# 02_Top_Level.net
KiCad netlist of a schematic drawn in Altium Designer
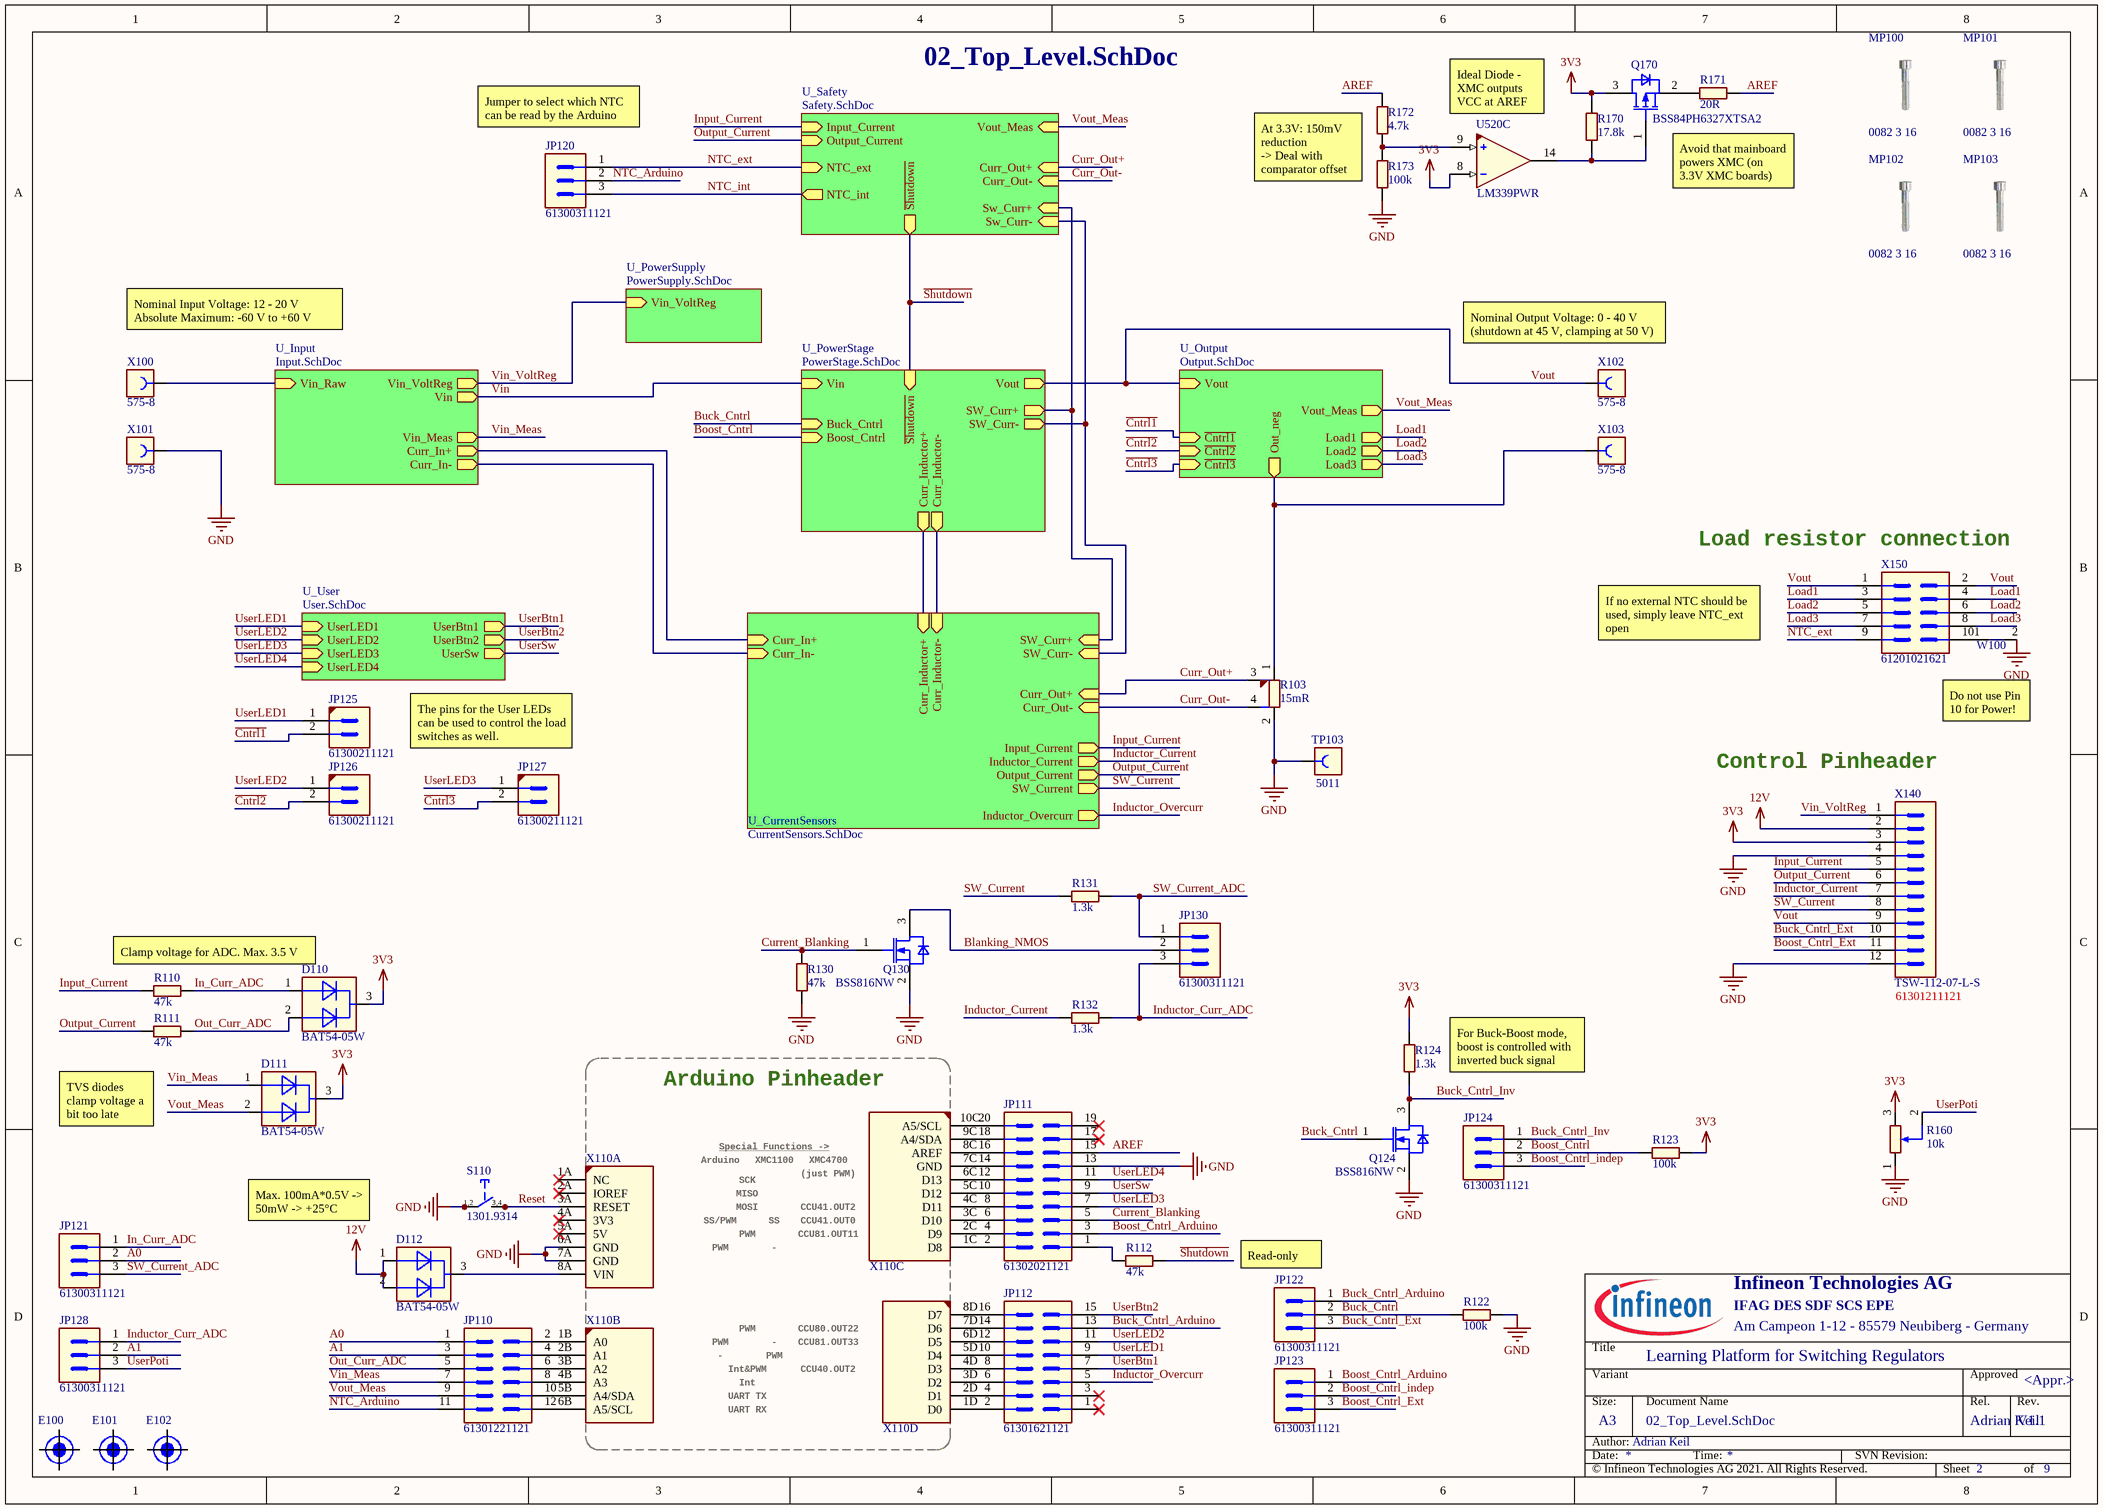
[diagram p0: 02_Top_Level.SchDoc]

(export (version "E")
  (design (tool "Eeschema 10.0.6"))
  (components
    (comp (ref "D110")
      (value "BAT54-05W")
      (footprint "SOT65P210X100-3N-1-V")
      (description "Silicon Schottky Diode, VR 30V")
      (fields (field (name "MANUFACTURER") "Infineon Technologies"))
      (libsource (lib "PCBLibraryData") (part "d_dual_a1a2c3_3p"))
    )
    (comp (ref "D111")
      (value "BAT54-05W")
      (footprint "SOT65P210X100-3N-1-V")
      (description "Silicon Schottky Diode, VR 30V")
      (fields (field (name "MANUFACTURER") "Infineon Technologies"))
      (libsource (lib "PCBLibraryData") (part "d_dual_a1a2c3_3p"))
    )
    (comp (ref "D112")
      (value "BAT54-05W")
      (footprint "SOT65P210X100-3N-1-V")
      (description "Silicon Schottky Diode, VR 30V")
      (fields (field (name "MANUFACTURER") "Infineon Technologies"))
      (libsource (lib "PCBLibraryData") (part "d_dual_a1a2c3_3p"))
    )
    (comp (ref "E100")
      (value "~")
      (footprint "fiducial")
      (description "Fiducial Mark")
      (fields
        (field (name "LEGACY PARTNUMBER") "MEC10000008")
        (field (name "MANUFACTURER") "Infineon Technologies")
      )
      (libsource (lib "PCBLibraryData") (part "fiducial"))
    )
    (comp (ref "E101")
      (value "~")
      (footprint "fiducial")
      (description "Fiducial Mark")
      (fields
        (field (name "LEGACY PARTNUMBER") "MEC10000008")
        (field (name "MANUFACTURER") "Infineon Technologies")
      )
      (libsource (lib "PCBLibraryData") (part "fiducial"))
    )
    (comp (ref "E102")
      (value "~")
      (footprint "fiducial")
      (description "Fiducial Mark")
      (fields
        (field (name "LEGACY PARTNUMBER") "MEC10000008")
        (field (name "MANUFACTURER") "Infineon Technologies")
      )
      (libsource (lib "PCBLibraryData") (part "fiducial"))
    )
    (comp (ref "JP110")
      (value "61301221121")
      (footprint "CON-M-THT-61301221121")
      (description "WR-PHD Dual Pin Header, 2.54mm Pitch, Double row, 12 Pins")
      (fields (field (name "MANUFACTURER") "Wurth Elektronik"))
      (libsource (lib "PCBLibraryData") (part "Header 6x2"))
    )
    (comp (ref "JP111")
      (value "61302021121")
      (footprint "CON-M-THT-61302021121")
      (description "WR-PHD Dual Pin Header, 2.54mm Pitch, Double row, 20 Pins")
      (fields (field (name "MANUFACTURER") "Wurth Elektronik"))
      (libsource (lib "PCBLibraryData") (part "Header 10X2"))
    )
    (comp (ref "JP112")
      (value "61301621121")
      (footprint "CON-M-THT-61301621121")
      (description "Connector Header Through Hole 16 position 0.100 (2.54mm)")
      (fields (field (name "MANUFACTURER") "Wurth Elektronik"))
      (libsource (lib "PCBLibraryData") (part "Header 8X2"))
    )
    (comp (ref "JP120")
      (value "61300311121")
      (footprint "CON-M-THT-61300311121")
      (description "WR-PHD Pin Header")
      (fields (field (name "MANUFACTURER") "Wurth Elektronik"))
      (libsource (lib "PCBLibraryData") (part "Header 3"))
    )
    (comp (ref "JP121")
      (value "61300311121")
      (footprint "CON-M-THT-61300311121")
      (description "WR-PHD Pin Header")
      (fields (field (name "MANUFACTURER") "Wurth Elektronik"))
      (libsource (lib "PCBLibraryData") (part "Header 3"))
    )
    (comp (ref "JP122")
      (value "61300311121")
      (footprint "CON-M-THT-61300311121")
      (description "WR-PHD Pin Header")
      (fields (field (name "MANUFACTURER") "Wurth Elektronik"))
      (libsource (lib "PCBLibraryData") (part "Header 3"))
    )
    (comp (ref "JP123")
      (value "61300311121")
      (footprint "CON-M-THT-61300311121")
      (description "WR-PHD Pin Header")
      (fields (field (name "MANUFACTURER") "Wurth Elektronik"))
      (libsource (lib "PCBLibraryData") (part "Header 3"))
    )
    (comp (ref "JP124")
      (value "61300311121")
      (footprint "CON-M-THT-61300311121")
      (description "WR-PHD Pin Header")
      (fields (field (name "MANUFACTURER") "Wurth Elektronik"))
      (libsource (lib "PCBLibraryData") (part "Header 3"))
    )
    (comp (ref "JP125")
      (value "61300211121")
      (footprint "CON-M-THT-61300211121")
      (description "Header, 2.54mm Pitch, 2 pin, Vertical, Single Row")
      (fields
        (field (name "LEGACY PARTNUMBER") "CON01500943")
        (field (name "MANUFACTURER") "Wurth Elektronik")
      )
      (libsource (lib "PCBLibraryData") (part "Header 2"))
    )
    (comp (ref "JP126")
      (value "61300211121")
      (footprint "CON-M-THT-61300211121")
      (description "Header, 2.54mm Pitch, 2 pin, Vertical, Single Row")
      (fields
        (field (name "LEGACY PARTNUMBER") "CON01500943")
        (field (name "MANUFACTURER") "Wurth Elektronik")
      )
      (libsource (lib "PCBLibraryData") (part "Header 2"))
    )
    (comp (ref "JP127")
      (value "61300211121")
      (footprint "CON-M-THT-61300211121")
      (description "Header, 2.54mm Pitch, 2 pin, Vertical, Single Row")
      (fields
        (field (name "LEGACY PARTNUMBER") "CON01500943")
        (field (name "MANUFACTURER") "Wurth Elektronik")
      )
      (libsource (lib "PCBLibraryData") (part "Header 2"))
    )
    (comp (ref "JP128")
      (value "61300311121")
      (footprint "CON-M-THT-61300311121")
      (description "WR-PHD Pin Header")
      (fields (field (name "MANUFACTURER") "Wurth Elektronik"))
      (libsource (lib "PCBLibraryData") (part "Header 3"))
    )
    (comp (ref "JP130")
      (value "61300311121")
      (footprint "CON-M-THT-61300311121")
      (description "WR-PHD Pin Header")
      (fields (field (name "MANUFACTURER") "Wurth Elektronik"))
      (libsource (lib "") (part "Header 3_1"))
    )
    (comp (ref "MP100")
      (value "0082 3 16")
      (footprint "SCREW_0082 3 16_NPTH")
      (description "Cheese Head Screw With Hexagon Socket, DIN 912 (ISO 4762), M3, 16mm length")
      (fields
        (field (name "LEGACY PARTNUMBER") "MEC10000167")
        (field (name "MANUFACTURER") "Wurth Elektronik")
      )
      (libsource (lib "PCBLibraryData") (part "Screw_0082 3 16"))
    )
    (comp (ref "MP101")
      (value "0082 3 16")
      (footprint "SCREW_0082 3 16_NPTH")
      (description "Cheese Head Screw With Hexagon Socket, DIN 912 (ISO 4762), M3, 16mm length")
      (fields
        (field (name "LEGACY PARTNUMBER") "MEC10000167")
        (field (name "MANUFACTURER") "Wurth Elektronik")
      )
      (libsource (lib "PCBLibraryData") (part "Screw_0082 3 16"))
    )
    (comp (ref "MP102")
      (value "0082 3 16")
      (footprint "SCREW_0082 3 16_NPTH")
      (description "Cheese Head Screw With Hexagon Socket, DIN 912 (ISO 4762), M3, 16mm length")
      (fields
        (field (name "LEGACY PARTNUMBER") "MEC10000167")
        (field (name "MANUFACTURER") "Wurth Elektronik")
      )
      (libsource (lib "PCBLibraryData") (part "Screw_0082 3 16"))
    )
    (comp (ref "MP103")
      (value "0082 3 16")
      (footprint "SCREW_0082 3 16_NPTH")
      (description "Cheese Head Screw With Hexagon Socket, DIN 912 (ISO 4762), M3, 16mm length")
      (fields
        (field (name "LEGACY PARTNUMBER") "MEC10000167")
        (field (name "MANUFACTURER") "Wurth Elektronik")
      )
      (libsource (lib "PCBLibraryData") (part "Screw_0082 3 16"))
    )
    (comp (ref "Q124")
      (value "BSS816NW")
      (footprint "SOT65P210X100-3N-1-V")
      (description "OptiMOS 2 Small-Signal-Transistor")
      (fields (field (name "MANUFACTURER") "Infineon Technologies"))
      (libsource (lib "PCBLibraryData") (part "igfet_n_ch_dep_dio_1g2s3d_3p"))
    )
    (comp (ref "Q130")
      (value "BSS816NW")
      (footprint "SOT65P210X100-3N-1-V")
      (description "OptiMOS 2 Small-Signal-Transistor")
      (fields (field (name "MANUFACTURER") "Infineon Technologies"))
      (libsource (lib "PCBLibraryData") (part "igfet_n_ch_dep_dio_1g2s3d_3p"))
    )
    (comp (ref "Q170")
      (value "BSS84PH6327XTSA2")
      (footprint "SOT95P240X110-3N-1")
      (description "SIPMOS P-Channel Enhancement Small-Signal-Transistor")
      (fields
        (field (name "LEGACY PARTNUMBER") "IFX01400461")
        (field (name "MANUFACTURER") "Infineon Technologies")
      )
      (libsource (lib "PCBLibraryData") (part "igfet_p_ch_enh_dio_1g2s3d_3p"))
    )
    (comp (ref "R103")
      (value "15mR")
      (footprint "RES-SMD-L4T12")
      (description "RES / STD / 15mR / 500mW / 1% / 75ppm/K / -55°C to 155°C / 1206 (3216) / SMD / -")
      (fields (field (name "MANUFACTURER") "Ohmite"))
      (libsource (lib "PCBLibraryData") (part "RES-SHT-STD-04P_00097BE5"))
    )
    (comp (ref "R110")
      (value "47k")
      (footprint "RESC1609X50N")
      (description "RES / STD / 47k / 100mW / 1% / 100ppm/K / -55°C to 155°C / 0603 / SMD / -")
      (fields (field (name "LEGACY PARTNUMBER") "RES01801333") (field (name "MANUFACTURER") "Vishay"))
      (libsource (lib "PCBLibraryData") (part "RES-SGL-STD-02P_00000006"))
    )
    (comp (ref "R111")
      (value "47k")
      (footprint "RESC1609X50N")
      (description "RES / STD / 47k / 100mW / 1% / 100ppm/K / -55°C to 155°C / 0603 / SMD / -")
      (fields (field (name "LEGACY PARTNUMBER") "RES01801333") (field (name "MANUFACTURER") "Vishay"))
      (libsource (lib "PCBLibraryData") (part "RES-SGL-STD-02P_00000006"))
    )
    (comp (ref "R112")
      (value "47k")
      (footprint "RESC1609X50N")
      (description "RES / STD / 47k / 100mW / 1% / 100ppm/K / -55°C to 155°C / 0603 / SMD / -")
      (fields (field (name "LEGACY PARTNUMBER") "RES01801333") (field (name "MANUFACTURER") "Vishay"))
      (libsource (lib "PCBLibraryData") (part "RES-SGL-STD-02P_00000006"))
    )
    (comp (ref "R122")
      (value "100k")
      (footprint "RESC1609X50N")
      (description "RES / STD / 100k / 100mW / 1% / 100ppm/K / -55°C to 155°C / 0603 / SMD / -")
      (fields (field (name "LEGACY PARTNUMBER") "RES01801371") (field (name "MANUFACTURER") "Vishay"))
      (libsource (lib "PCBLibraryData") (part "RES-SGL-STD-02P_00000006"))
    )
    (comp (ref "R123")
      (value "100k")
      (footprint "RESC1609X50N")
      (description "RES / STD / 100k / 100mW / 1% / 100ppm/K / -55°C to 155°C / 0603 / SMD / -")
      (fields (field (name "LEGACY PARTNUMBER") "RES01801371") (field (name "MANUFACTURER") "Vishay"))
      (libsource (lib "PCBLibraryData") (part "RES-SGL-STD-02P_00000006"))
    )
    (comp (ref "R124")
      (value "1.3k")
      (footprint "RESC1609X50N")
      (description "RES / STD / 1.3k / 100mW / 1% / 100ppm/K / -55°C to 155°C / 0603 / SMD / -")
      (fields (field (name "LEGACY PARTNUMBER") "RES01801155") (field (name "MANUFACTURER") "Vishay"))
      (libsource (lib "") (part "RES-SGL-STD-02P_00000006_1"))
    )
    (comp (ref "R130")
      (value "47k")
      (footprint "RESC1609X50N")
      (description "RES / STD / 47k / 100mW / 1% / 100ppm/K / -55°C to 155°C / 0603 / SMD / -")
      (fields (field (name "LEGACY PARTNUMBER") "RES01801333") (field (name "MANUFACTURER") "Vishay"))
      (libsource (lib "") (part "RES-SGL-STD-02P_00000006_1"))
    )
    (comp (ref "R131")
      (value "1.3k")
      (footprint "RESC1609X50N")
      (description "RES / STD / 1.3k / 100mW / 1% / 100ppm/K / -55°C to 155°C / 0603 / SMD / -")
      (fields (field (name "LEGACY PARTNUMBER") "RES01801155") (field (name "MANUFACTURER") "Vishay"))
      (libsource (lib "PCBLibraryData") (part "RES-SGL-STD-02P_00000006"))
    )
    (comp (ref "R132")
      (value "1.3k")
      (footprint "RESC1609X50N")
      (description "RES / STD / 1.3k / 100mW / 1% / 100ppm/K / -55°C to 155°C / 0603 / SMD / -")
      (fields (field (name "LEGACY PARTNUMBER") "RES01801155") (field (name "MANUFACTURER") "Vishay"))
      (libsource (lib "PCBLibraryData") (part "RES-SGL-STD-02P_00000006"))
    )
    (comp (ref "R160")
      (value "10k")
      (footprint "POT-SMD-3361P")
      (fields (field (name "MANUFACTURER") "Bourns"))
      (libsource (lib "PCBLibraryData") (part "RES-SGL-VAR-03P_00000026"))
    )
    (comp (ref "R170")
      (value "17.8k")
      (footprint "RESC1609X50N")
      (description "RES / STD / 17.8k / 100mW / 1% / 100ppm/K / -55°C to 155°C / 0603 / SMD / -")
      (fields (field (name "LEGACY PARTNUMBER") "RES01801283") (field (name "MANUFACTURER") "Vishay"))
      (libsource (lib "") (part "RES-SGL-STD-02P_00000006_2"))
    )
    (comp (ref "R171")
      (value "20R")
      (footprint "RESC1609X50N")
      (description "RES / STD / 20R / 100mW / 1% / 100ppm/K / -55°C to 155°C / 0603 / SMD / -")
      (fields (field (name "LEGACY PARTNUMBER") "RES01800947") (field (name "MANUFACTURER") "Vishay"))
      (libsource (lib "PCBLibraryData") (part "RES-SGL-STD-02P_00000006"))
    )
    (comp (ref "R172")
      (value "4.7k")
      (footprint "RESC1609X50N")
      (description "RES / STD / 4.7k / 100mW / 1% / 100ppm/K / -55°C to 155°C / 0603 / SMD / -")
      (fields (field (name "LEGACY PARTNUMBER") "RES01801219") (field (name "MANUFACTURER") "Vishay"))
      (libsource (lib "") (part "RES-SGL-STD-02P_00000006_2"))
    )
    (comp (ref "R173")
      (value "100k")
      (footprint "RESC1609X50N")
      (description "RES / STD / 100k / 100mW / 1% / 100ppm/K / -55°C to 155°C / 0603 / SMD / -")
      (fields (field (name "LEGACY PARTNUMBER") "RES01801371") (field (name "MANUFACTURER") "Vishay"))
      (libsource (lib "") (part "RES-SGL-STD-02P_00000006_1"))
    )
    (comp (ref "S110")
      (value "1301.9314")
      (footprint "SW-SMD-1301.9314")
      (description "Pushbutton Tactile Switch, Single Pole Single Throw, 4 Pins")
      (fields (field (name "LEGACY PARTNUMBER") "CON01500305") (field (name "MANUFACTURER") "Schurter"))
      (libsource (lib "PCBLibraryData") (part "sw_sr_no12_34_4p"))
    )
    (comp (ref "TP103")
      (value "5011")
      (footprint "CON-THT-TP-5011")
      (description "PC Test Point-Multipurpose THT, Black")
      (fields
        (field (name "LEGACY PARTNUMBER") "CON01500530")
        (field (name "MANUFACTURER") "Keystone Electronics Corp.")
      )
      (libsource (lib "PCBLibraryData") (part "connector_1_f"))
    )
    (comp (ref "U520")
      (value "LM339PWR")
      (footprint "SOP65P640X120-14N-1")
      (description "Quad Differential Comparator")
      (fields
        (field (name "LEGACY PARTNUMBER") "IC02600564")
        (field (name "MANUFACTURER") "Texas Instruments")
      )
      (libsource (lib "PCBLibraryData") (part "LM339PWR"))
    )
    (comp (ref "W100")
      (value "Net_Tie_2")
      (footprint "Net_Tie_Small_2P")
      (description "SMD Net Tie for two Nets")
      (fields
        (field (name "LEGACY PARTNUMBER") "CON01501379")
        (field (name "MANUFACTURER") "Infineon Technologies")
      )
      (libsource (lib "PCBLibraryData") (part "Net_Tie_2"))
    )
    (comp (ref "X100")
      (value "575-8")
      (footprint "CON-F-TH-575-6")
      (description "Non Insulated Jack, Brass")
      (fields (field (name "MANUFACTURER") "Keystone Electronics Corp."))
      (libsource (lib "") (part "connector_1_f_2"))
    )
    (comp (ref "X101")
      (value "575-8")
      (footprint "CON-F-TH-575-6")
      (description "Non Insulated Jack, Brass")
      (fields (field (name "MANUFACTURER") "Keystone Electronics Corp."))
      (libsource (lib "") (part "connector_1_f_2"))
    )
    (comp (ref "X102")
      (value "575-8")
      (footprint "CON-F-TH-575-6")
      (description "Non Insulated Jack, Brass")
      (fields (field (name "MANUFACTURER") "Keystone Electronics Corp."))
      (libsource (lib "") (part "connector_1_f_1"))
    )
    (comp (ref "X103")
      (value "575-8")
      (footprint "CON-F-TH-575-6")
      (description "Non Insulated Jack, Brass")
      (fields (field (name "MANUFACTURER") "Keystone Electronics Corp."))
      (libsource (lib "") (part "connector_1_f_1"))
    )
    (comp (ref "X110")
      (value "Arduino-Uno")
      (footprint "Arduino-Uno")
      (description "Arduino Uno is a microcontroller board based on the ATmega328P")
      (fields (field (name "MANUFACTURER") "Infineon Technologies"))
      (libsource (lib "PCBLibraryData") (part "Arduino-Uno"))
    )
    (comp (ref "X140")
      (value "TSW-112-07-L-S")
      (footprint "HDRV12W64P254_1X12_3048X254X898B")
      (description "Through hole .025 SQ Post Header, 2.54mm pitch, 12 pin, vertical, single row")
      (fields (field (name "LEGACY PARTNUMBER") "CON01500432") (field (name "MANUFACTURER") "Samtec"))
      (libsource (lib "PCBLibraryData") (part "Header 12"))
    )
    (comp (ref "X150")
      (value "61201021621")
      (footprint "CON-M-THT-61201021621")
      (description "WR-BHD Male Box Header, 2.54mm pitch, 10 pin, Vertical, Double row")
      (fields (field (name "MANUFACTURER") "Wurth Elektronik"))
      (libsource (lib "PCBLibraryData") (part "Header 5X2"))
    )
  )
  (nets
    (net (code "1") (name "/A0") (class "Default")
      (node (ref "JP110") (pin "1") (pinfunction "1_1") (pintype "passive"))
      (node (ref "JP121") (pin "2") (pinfunction "2_2") (pintype "passive"))
    )
    (net (code "2") (name "/A1") (class "Default")
      (node (ref "JP110") (pin "3") (pinfunction "3_3") (pintype "passive"))
      (node (ref "JP128") (pin "2") (pinfunction "2_2") (pintype "passive"))
    )
    (net (code "3") (name "/AREF") (class "Default")
      (node (ref "JP111") (pin "15") (pinfunction "15_15") (pintype "passive"))
      (node (ref "R171") (pin "1") (pinfunction "1_1") (pintype "passive"))
      (node (ref "R172") (pin "1") (pinfunction "1_1") (pintype "passive"))
    )
    (net (code "4") (name "/Blanking_NMOS") (class "Default")
      (node (ref "JP130") (pin "2") (pinfunction "2_2") (pintype "passive"))
      (node (ref "Q130") (pin "3") (pinfunction "DRAIN_3") (pintype "passive"))
    )
    (net (code "5") (name "/Boost_Cntrl") (class "Default")
      (node (ref "JP124") (pin "2") (pinfunction "2_2") (pintype "passive"))
      (node (ref "R123") (pin "2") (pinfunction "2_2") (pintype "passive"))
    )
    (net (code "6") (name "/Boost_Cntrl_Arduino") (class "Default")
      (node (ref "JP111") (pin "3") (pinfunction "3_3") (pintype "passive"))
      (node (ref "JP123") (pin "1") (pinfunction "1_1") (pintype "passive"))
    )
    (net (code "7") (name "/Boost_Cntrl_Ext") (class "Default")
      (node (ref "JP123") (pin "3") (pinfunction "3_3") (pintype "passive"))
      (node (ref "X140") (pin "11") (pinfunction "11_11") (pintype "passive"))
    )
    (net (code "8") (name "/Boost_Cntrl_indep") (class "Default")
      (node (ref "JP123") (pin "2") (pinfunction "2_2") (pintype "passive"))
      (node (ref "JP124") (pin "3") (pinfunction "3_3") (pintype "passive"))
    )
    (net (code "9") (name "/Buck_Cntrl") (class "Default")
      (node (ref "JP122") (pin "2") (pinfunction "2_2") (pintype "passive"))
      (node (ref "Q124") (pin "1") (pinfunction "GATE_1") (pintype "passive"))
      (node (ref "R122") (pin "2") (pinfunction "2_2") (pintype "passive"))
    )
    (net (code "10") (name "/Buck_Cntrl_Arduino") (class "Default")
      (node (ref "JP112") (pin "13") (pinfunction "13_13") (pintype "passive"))
      (node (ref "JP122") (pin "1") (pinfunction "1_1") (pintype "passive"))
    )
    (net (code "11") (name "/Buck_Cntrl_Ext") (class "Default")
      (node (ref "JP122") (pin "3") (pinfunction "3_3") (pintype "passive"))
      (node (ref "X140") (pin "10") (pinfunction "10_10") (pintype "passive"))
    )
    (net (code "12") (name "/Buck_Cntrl_Inv") (class "Default")
      (node (ref "JP124") (pin "1") (pinfunction "1_1") (pintype "passive"))
      (node (ref "Q124") (pin "3") (pinfunction "DRAIN_3") (pintype "passive"))
      (node (ref "R124") (pin "1") (pinfunction "1_1") (pintype "passive"))
    )
    (net (code "13") (name "/Cntrl1") (class "Default")
      (node (ref "JP125") (pin "2") (pinfunction "2_2") (pintype "passive"))
    )
    (net (code "14") (name "/Cntrl2") (class "Default")
      (node (ref "JP126") (pin "2") (pinfunction "2_2") (pintype "passive"))
    )
    (net (code "15") (name "/Cntrl3") (class "Default")
      (node (ref "JP127") (pin "2") (pinfunction "2_2") (pintype "passive"))
    )
    (net (code "20") (name "/Curr_Out+") (class "Default")
      (node (ref "R103") (pin "3") (pinfunction "I1_3") (pintype "passive"))
    )
    (net (code "21") (name "/Curr_Out-") (class "Default")
      (node (ref "R103") (pin "4") (pinfunction "I2_4") (pintype "passive"))
    )
    (net (code "22") (name "/Current_Blanking") (class "Default")
      (node (ref "JP111") (pin "5") (pinfunction "5_5") (pintype "passive"))
      (node (ref "Q130") (pin "1") (pinfunction "GATE_1") (pintype "passive"))
      (node (ref "R130") (pin "2") (pinfunction "2_2") (pintype "passive"))
    )
    (net (code "23") (name "/In_Curr_ADC") (class "Default")
      (node (ref "D110") (pin "1") (pinfunction "ANODE_1_1") (pintype "passive"))
      (node (ref "JP121") (pin "1") (pinfunction "1_1") (pintype "passive"))
      (node (ref "R110") (pin "1") (pinfunction "1_1") (pintype "passive"))
    )
    (net (code "24") (name "/Inductor_Curr_ADC") (class "Default")
      (node (ref "JP128") (pin "1") (pinfunction "1_1") (pintype "passive"))
      (node (ref "JP130") (pin "3") (pinfunction "3_3") (pintype "passive"))
      (node (ref "R132") (pin "1") (pinfunction "1_1") (pintype "passive"))
    )
    (net (code "25") (name "/Inductor_Current") (class "Default")
      (node (ref "R132") (pin "2") (pinfunction "2_2") (pintype "passive"))
      (node (ref "X140") (pin "7") (pinfunction "7_7") (pintype "passive"))
    )
    (net (code "26") (name "/Inductor_Overcurr") (class "Default")
      (node (ref "JP112") (pin "5") (pinfunction "5_5") (pintype "passive"))
    )
    (net (code "27") (name "/Input_Current") (class "Default")
      (node (ref "R110") (pin "2") (pinfunction "2_2") (pintype "passive"))
      (node (ref "X140") (pin "5") (pinfunction "5_5") (pintype "passive"))
    )
    (net (code "28") (name "/Load1") (class "Default")
      (node (ref "X150") (pin "3") (pinfunction "3_3") (pintype "passive"))
      (node (ref "X150") (pin "4") (pinfunction "4_4") (pintype "passive"))
    )
    (net (code "29") (name "/Load2") (class "Default")
      (node (ref "X150") (pin "5") (pinfunction "5_5") (pintype "passive"))
      (node (ref "X150") (pin "6") (pinfunction "6_6") (pintype "passive"))
    )
    (net (code "30") (name "/Load3") (class "Default")
      (node (ref "X150") (pin "7") (pinfunction "7_7") (pintype "passive"))
      (node (ref "X150") (pin "8") (pinfunction "8_8") (pintype "passive"))
    )
    (net (code "31") (name "/NTC_Arduino") (class "Default")
      (node (ref "JP110") (pin "11") (pinfunction "11_11") (pintype "passive"))
      (node (ref "JP120") (pin "2") (pinfunction "2_2") (pintype "passive"))
    )
    (net (code "32") (name "/NTC_ext") (class "Default")
      (node (ref "JP120") (pin "1") (pinfunction "1_1") (pintype "passive"))
      (node (ref "X150") (pin "9") (pinfunction "9_9") (pintype "passive"))
    )
    (net (code "33") (name "/NTC_int") (class "Default")
      (node (ref "JP120") (pin "3") (pinfunction "3_3") (pintype "passive"))
    )
    (net (code "34") (name "/Out_Curr_ADC") (class "Default")
      (node (ref "D110") (pin "2") (pinfunction "ANODE_2_2") (pintype "passive"))
      (node (ref "JP110") (pin "5") (pinfunction "5_5") (pintype "passive"))
      (node (ref "R111") (pin "1") (pinfunction "1_1") (pintype "passive"))
    )
    (net (code "35") (name "/Out_neg") (class "Default")
      (node (ref "R103") (pin "1") (pinfunction "V1_1") (pintype "passive"))
      (node (ref "X103") (pin "1") (pinfunction "1_1") (pintype "passive"))
    )
    (net (code "36") (name "/Output_Current") (class "Default")
      (node (ref "R111") (pin "2") (pinfunction "2_2") (pintype "passive"))
      (node (ref "X140") (pin "6") (pinfunction "6_6") (pintype "passive"))
    )
    (net (code "37") (name "/Reset") (class "Default")
      (node (ref "S110") (pin "3") (pinfunction "3_3") (pintype "passive"))
      (node (ref "S110") (pin "4") (pinfunction "4_4") (pintype "passive"))
      (node (ref "X110") (pin "3A") (pinfunction "RESET_3A") (pintype "passive"))
    )
    (net (code "40") (name "/SW_Current") (class "Default")
      (node (ref "R131") (pin "2") (pinfunction "2_2") (pintype "passive"))
      (node (ref "X140") (pin "8") (pinfunction "8_8") (pintype "passive"))
    )
    (net (code "41") (name "/SW_Current_ADC") (class "Default")
      (node (ref "JP121") (pin "3") (pinfunction "3_3") (pintype "passive"))
      (node (ref "JP130") (pin "1") (pinfunction "1_1") (pintype "passive"))
      (node (ref "R131") (pin "1") (pinfunction "1_1") (pintype "passive"))
    )
    (net (code "42") (name "/Shutdown") (class "Default")
      (node (ref "R112") (pin "1") (pinfunction "1_1") (pintype "passive"))
    )
    (net (code "43") (name "/UserBtn1") (class "Default")
      (node (ref "JP112") (pin "7") (pinfunction "7_7") (pintype "passive"))
    )
    (net (code "44") (name "/UserBtn2") (class "Default")
      (node (ref "JP112") (pin "15") (pinfunction "15_15") (pintype "passive"))
    )
    (net (code "45") (name "/UserLED1") (class "Default")
      (node (ref "JP112") (pin "9") (pinfunction "9_9") (pintype "passive"))
      (node (ref "JP125") (pin "1") (pinfunction "1_1") (pintype "passive"))
    )
    (net (code "46") (name "/UserLED2") (class "Default")
      (node (ref "JP112") (pin "11") (pinfunction "11_11") (pintype "passive"))
      (node (ref "JP126") (pin "1") (pinfunction "1_1") (pintype "passive"))
    )
    (net (code "47") (name "/UserLED3") (class "Default")
      (node (ref "JP111") (pin "7") (pinfunction "7_7") (pintype "passive"))
      (node (ref "JP127") (pin "1") (pinfunction "1_1") (pintype "passive"))
    )
    (net (code "48") (name "/UserLED4") (class "Default")
      (node (ref "JP111") (pin "11") (pinfunction "11_11") (pintype "passive"))
    )
    (net (code "49") (name "/UserPoti") (class "Default")
      (node (ref "JP128") (pin "3") (pinfunction "3_3") (pintype "passive"))
      (node (ref "R160") (pin "2") (pinfunction "2_2") (pintype "passive"))
    )
    (net (code "50") (name "/UserSw") (class "Default")
      (node (ref "JP111") (pin "9") (pinfunction "9_9") (pintype "passive"))
    )
    (net (code "52") (name "/Vin_Meas") (class "Default")
      (node (ref "D111") (pin "1") (pinfunction "ANODE_1_1") (pintype "passive"))
      (node (ref "JP110") (pin "7") (pinfunction "7_7") (pintype "passive"))
    )
    (net (code "53") (name "/Vin_Raw") (class "Default")
      (node (ref "X100") (pin "1") (pinfunction "1_1") (pintype "passive"))
    )
    (net (code "54") (name "/Vin_VoltReg") (class "Default")
      (node (ref "X140") (pin "1") (pinfunction "1_1") (pintype "passive"))
    )
    (net (code "55") (name "/Vout") (class "Default")
      (node (ref "X102") (pin "1") (pinfunction "1_1") (pintype "passive"))
      (node (ref "X140") (pin "9") (pinfunction "9_9") (pintype "passive"))
      (node (ref "X150") (pin "1") (pinfunction "1_1") (pintype "passive"))
      (node (ref "X150") (pin "2") (pinfunction "2_2") (pintype "passive"))
    )
    (net (code "56") (name "/Vout_Meas") (class "Default")
      (node (ref "D111") (pin "2") (pinfunction "ANODE_2_2") (pintype "passive"))
      (node (ref "JP110") (pin "9") (pinfunction "9_9") (pintype "passive"))
    )
    (net (code "57") (name "3V3") (class "Default")
      (node (ref "D110") (pin "3") (pinfunction "CATHODE_3") (pintype "passive"))
      (node (ref "D111") (pin "3") (pinfunction "CATHODE_3") (pintype "passive"))
      (node (ref "Q170") (pin "3") (pinfunction "DRAIN_3") (pintype "passive"))
      (node (ref "R123") (pin "1") (pinfunction "1_1") (pintype "passive"))
      (node (ref "R124") (pin "2") (pinfunction "2_2") (pintype "passive"))
      (node (ref "R160") (pin "3") (pinfunction "3_3") (pintype "passive"))
      (node (ref "R170") (pin "1") (pinfunction "1_1") (pintype "passive"))
      (node (ref "U520") (pin "8") (pinfunction "3IN_N_8") (pintype "input"))
      (node (ref "X140") (pin "3") (pinfunction "3_3") (pintype "passive"))
    )
    (net (code "58") (name "12V") (class "Default")
      (node (ref "D112") (pin "1") (pinfunction "ANODE_1_1") (pintype "passive"))
      (node (ref "D112") (pin "2") (pinfunction "ANODE_2_2") (pintype "passive"))
      (node (ref "X140") (pin "2") (pinfunction "2_2") (pintype "passive"))
    )
    (net (code "59") (name "GND") (class "Default")
      (node (ref "JP111") (pin "13") (pinfunction "13_13") (pintype "passive"))
      (node (ref "Q124") (pin "2") (pinfunction "SOURCE_2") (pintype "passive"))
      (node (ref "Q130") (pin "2") (pinfunction "SOURCE_2") (pintype "passive"))
      (node (ref "R103") (pin "2") (pinfunction "V2_2") (pintype "passive"))
      (node (ref "R122") (pin "1") (pinfunction "1_1") (pintype "passive"))
      (node (ref "R130") (pin "1") (pinfunction "1_1") (pintype "passive"))
      (node (ref "R160") (pin "1") (pinfunction "1_1") (pintype "passive"))
      (node (ref "R173") (pin "1") (pinfunction "1_1") (pintype "passive"))
      (node (ref "S110") (pin "1") (pinfunction "1_1") (pintype "passive"))
      (node (ref "S110") (pin "2") (pinfunction "2_2") (pintype "passive"))
      (node (ref "TP103") (pin "1") (pinfunction "1_1") (pintype "passive"))
      (node (ref "W100") (pin "2") (pinfunction "2_2") (pintype "passive"))
      (node (ref "X101") (pin "1") (pinfunction "1_1") (pintype "passive"))
      (node (ref "X110") (pin "6A") (pinfunction "GND_6A") (pintype "passive"))
      (node (ref "X110") (pin "7A") (pinfunction "GND_7A") (pintype "passive"))
      (node (ref "X140") (pin "12") (pinfunction "12_12") (pintype "passive"))
      (node (ref "X140") (pin "4") (pinfunction "4_4") (pintype "passive"))
    )
    (net (code "60") (name "Net-(D112-CATHODE)") (class "Default")
      (node (ref "D112") (pin "3") (pinfunction "CATHODE_3") (pintype "passive"))
      (node (ref "X110") (pin "8A") (pinfunction "VIN_8A") (pintype "passive"))
    )
    (net (code "61") (name "Net-(JP111-Pad1)") (class "Default")
      (node (ref "JP111") (pin "1") (pinfunction "1_1") (pintype "passive"))
      (node (ref "R112") (pin "2") (pinfunction "2_2") (pintype "passive"))
    )
    (net (code "62") (name "Net-(Q170-GATE)") (class "Default")
      (node (ref "Q170") (pin "1") (pinfunction "GATE_1") (pintype "passive"))
      (node (ref "R170") (pin "2") (pinfunction "2_2") (pintype "passive"))
      (node (ref "U520") (pin "14") (pinfunction "3OUT_14") (pintype "open_collector"))
    )
    (net (code "63") (name "Net-(Q170-SOURCE)") (class "Default")
      (node (ref "Q170") (pin "2") (pinfunction "SOURCE_2") (pintype "passive"))
      (node (ref "R171") (pin "2") (pinfunction "2_2") (pintype "passive"))
    )
    (net (code "64") (name "Net-(U520C-3IN_P)") (class "Default")
      (node (ref "R172") (pin "2") (pinfunction "2_2") (pintype "passive"))
      (node (ref "R173") (pin "2") (pinfunction "2_2") (pintype "passive"))
      (node (ref "U520") (pin "9") (pinfunction "3IN_P_9") (pintype "input"))
    )
    (net (code "65") (name "Net-(W100-Pad1)") (class "Default")
      (node (ref "W100") (pin "1") (pinfunction "1_1") (pintype "passive"))
      (node (ref "X150") (pin "10") (pinfunction "10_10") (pintype "passive"))
    )
    (net (code "66") (name "Net-(X110B-A0)") (class "Default")
      (node (ref "JP110") (pin "2") (pinfunction "2_2") (pintype "passive"))
      (node (ref "X110") (pin "1B") (pinfunction "A0_1B") (pintype "passive"))
    )
    (net (code "67") (name "Net-(X110B-A1)") (class "Default")
      (node (ref "JP110") (pin "4") (pinfunction "4_4") (pintype "passive"))
      (node (ref "X110") (pin "2B") (pinfunction "A1_2B") (pintype "passive"))
    )
    (net (code "68") (name "Net-(X110B-A2)") (class "Default")
      (node (ref "JP110") (pin "6") (pinfunction "6_6") (pintype "passive"))
      (node (ref "X110") (pin "3B") (pinfunction "A2_3B") (pintype "passive"))
    )
    (net (code "69") (name "Net-(X110B-A3)") (class "Default")
      (node (ref "JP110") (pin "8") (pinfunction "8_8") (pintype "passive"))
      (node (ref "X110") (pin "4B") (pinfunction "A3_4B") (pintype "passive"))
    )
    (net (code "70") (name "Net-(X110B-A4{slash}SDA)") (class "Default")
      (node (ref "JP110") (pin "10") (pinfunction "10_10") (pintype "passive"))
      (node (ref "X110") (pin "5B") (pinfunction "A4/SDA_5B") (pintype "passive"))
    )
    (net (code "71") (name "Net-(X110B-A5{slash}SCL)") (class "Default")
      (node (ref "JP110") (pin "12") (pinfunction "12_12") (pintype "passive"))
      (node (ref "X110") (pin "6B") (pinfunction "A5/SCL_6B") (pintype "passive"))
    )
    (net (code "72") (name "Net-(X110C-A4{slash}SDA)") (class "Default")
      (node (ref "JP111") (pin "18") (pinfunction "18_18") (pintype "passive"))
      (node (ref "X110") (pin "9C") (pinfunction "A4/SDA_9C") (pintype "passive"))
    )
    (net (code "73") (name "Net-(X110C-A5{slash}SCL)") (class "Default")
      (node (ref "JP111") (pin "20") (pinfunction "20_20") (pintype "passive"))
      (node (ref "X110") (pin "10C") (pinfunction "A5/SCL_10C") (pintype "passive"))
    )
    (net (code "74") (name "Net-(X110C-AREF)") (class "Default")
      (node (ref "JP111") (pin "16") (pinfunction "16_16") (pintype "passive"))
      (node (ref "X110") (pin "8C") (pinfunction "AREF_8C") (pintype "passive"))
    )
    (net (code "75") (name "Net-(X110C-D8)") (class "Default")
      (node (ref "JP111") (pin "2") (pinfunction "2_2") (pintype "passive"))
      (node (ref "X110") (pin "1C") (pinfunction "D8_1C") (pintype "passive"))
    )
    (net (code "76") (name "Net-(X110C-D9)") (class "Default")
      (node (ref "JP111") (pin "4") (pinfunction "4_4") (pintype "passive"))
      (node (ref "X110") (pin "2C") (pinfunction "D9_2C") (pintype "passive"))
    )
    (net (code "77") (name "Net-(X110C-D10)") (class "Default")
      (node (ref "JP111") (pin "6") (pinfunction "6_6") (pintype "passive"))
      (node (ref "X110") (pin "3C") (pinfunction "D10_3C") (pintype "passive"))
    )
    (net (code "78") (name "Net-(X110C-D11)") (class "Default")
      (node (ref "JP111") (pin "8") (pinfunction "8_8") (pintype "passive"))
      (node (ref "X110") (pin "4C") (pinfunction "D11_4C") (pintype "passive"))
    )
    (net (code "79") (name "Net-(X110C-D12)") (class "Default")
      (node (ref "JP111") (pin "10") (pinfunction "10_10") (pintype "passive"))
      (node (ref "X110") (pin "5C") (pinfunction "D12_5C") (pintype "passive"))
    )
    (net (code "80") (name "Net-(X110C-D13)") (class "Default")
      (node (ref "JP111") (pin "12") (pinfunction "12_12") (pintype "passive"))
      (node (ref "X110") (pin "6C") (pinfunction "D13_6C") (pintype "passive"))
    )
    (net (code "81") (name "Net-(X110C-GND)") (class "Default")
      (node (ref "JP111") (pin "14") (pinfunction "14_14") (pintype "passive"))
      (node (ref "X110") (pin "7C") (pinfunction "GND_7C") (pintype "passive"))
    )
    (net (code "82") (name "Net-(X110D-D0)") (class "Default")
      (node (ref "JP112") (pin "2") (pinfunction "2_2") (pintype "passive"))
      (node (ref "X110") (pin "1D") (pinfunction "D0_1D") (pintype "passive"))
    )
    (net (code "83") (name "Net-(X110D-D1)") (class "Default")
      (node (ref "JP112") (pin "4") (pinfunction "4_4") (pintype "passive"))
      (node (ref "X110") (pin "2D") (pinfunction "D1_2D") (pintype "passive"))
    )
    (net (code "84") (name "Net-(X110D-D2)") (class "Default")
      (node (ref "JP112") (pin "6") (pinfunction "6_6") (pintype "passive"))
      (node (ref "X110") (pin "3D") (pinfunction "D2_3D") (pintype "passive"))
    )
    (net (code "85") (name "Net-(X110D-D3)") (class "Default")
      (node (ref "JP112") (pin "8") (pinfunction "8_8") (pintype "passive"))
      (node (ref "X110") (pin "4D") (pinfunction "D3_4D") (pintype "passive"))
    )
    (net (code "86") (name "Net-(X110D-D4)") (class "Default")
      (node (ref "JP112") (pin "10") (pinfunction "10_10") (pintype "passive"))
      (node (ref "X110") (pin "5D") (pinfunction "D4_5D") (pintype "passive"))
    )
    (net (code "87") (name "Net-(X110D-D5)") (class "Default")
      (node (ref "JP112") (pin "12") (pinfunction "12_12") (pintype "passive"))
      (node (ref "X110") (pin "6D") (pinfunction "D5_6D") (pintype "passive"))
    )
    (net (code "88") (name "Net-(X110D-D6)") (class "Default")
      (node (ref "JP112") (pin "14") (pinfunction "14_14") (pintype "passive"))
      (node (ref "X110") (pin "7D") (pinfunction "D6_7D") (pintype "passive"))
    )
    (net (code "89") (name "Net-(X110D-D7)") (class "Default")
      (node (ref "JP112") (pin "16") (pinfunction "16_16") (pintype "passive"))
      (node (ref "X110") (pin "8D") (pinfunction "D7_8D") (pintype "passive"))
    )
    (net (code "90") (name "unconnected-(E100-Pad1)") (class "Default")
      (node (ref "E100") (pin "1") (pinfunction "1_1") (pintype "passive"))
    )
    (net (code "91") (name "unconnected-(E101-Pad1)") (class "Default")
      (node (ref "E101") (pin "1") (pinfunction "1_1") (pintype "passive"))
    )
    (net (code "92") (name "unconnected-(E102-Pad1)") (class "Default")
      (node (ref "E102") (pin "1") (pinfunction "1_1") (pintype "passive"))
    )
    (net (code "93") (name "unconnected-(JP111-Pad17)") (class "Default")
      (node (ref "JP111") (pin "17") (pinfunction "17_17") (pintype "passive+no_connect"))
    )
    (net (code "94") (name "unconnected-(JP111-Pad19)") (class "Default")
      (node (ref "JP111") (pin "19") (pinfunction "19_19") (pintype "passive+no_connect"))
    )
    (net (code "95") (name "unconnected-(JP112-Pad1)") (class "Default")
      (node (ref "JP112") (pin "1") (pinfunction "1_1") (pintype "passive+no_connect"))
    )
    (net (code "96") (name "unconnected-(JP112-Pad3)") (class "Default")
      (node (ref "JP112") (pin "3") (pinfunction "3_3") (pintype "passive+no_connect"))
    )
    (net (code "97") (name "unconnected-(X110A-3V3-Pad4A)") (class "Default")
      (node (ref "X110") (pin "4A") (pinfunction "3V3_4A") (pintype "passive+no_connect"))
    )
    (net (code "98") (name "unconnected-(X110A-5V-Pad5A)") (class "Default")
      (node (ref "X110") (pin "5A") (pinfunction "5V_5A") (pintype "passive+no_connect"))
    )
    (net (code "99") (name "unconnected-(X110A-IOREF-Pad2A)") (class "Default")
      (node (ref "X110") (pin "2A") (pinfunction "IOREF_2A") (pintype "passive+no_connect"))
    )
    (net (code "100") (name "unconnected-(X110A-NC-Pad1A)") (class "Default")
      (node (ref "X110") (pin "1A") (pinfunction "NC_1A") (pintype "passive+no_connect"))
    )
  )
)
